# MOM-analog-ins_one-layer_v08.net
KiCad netlist of a schematic drawn in EAGLE
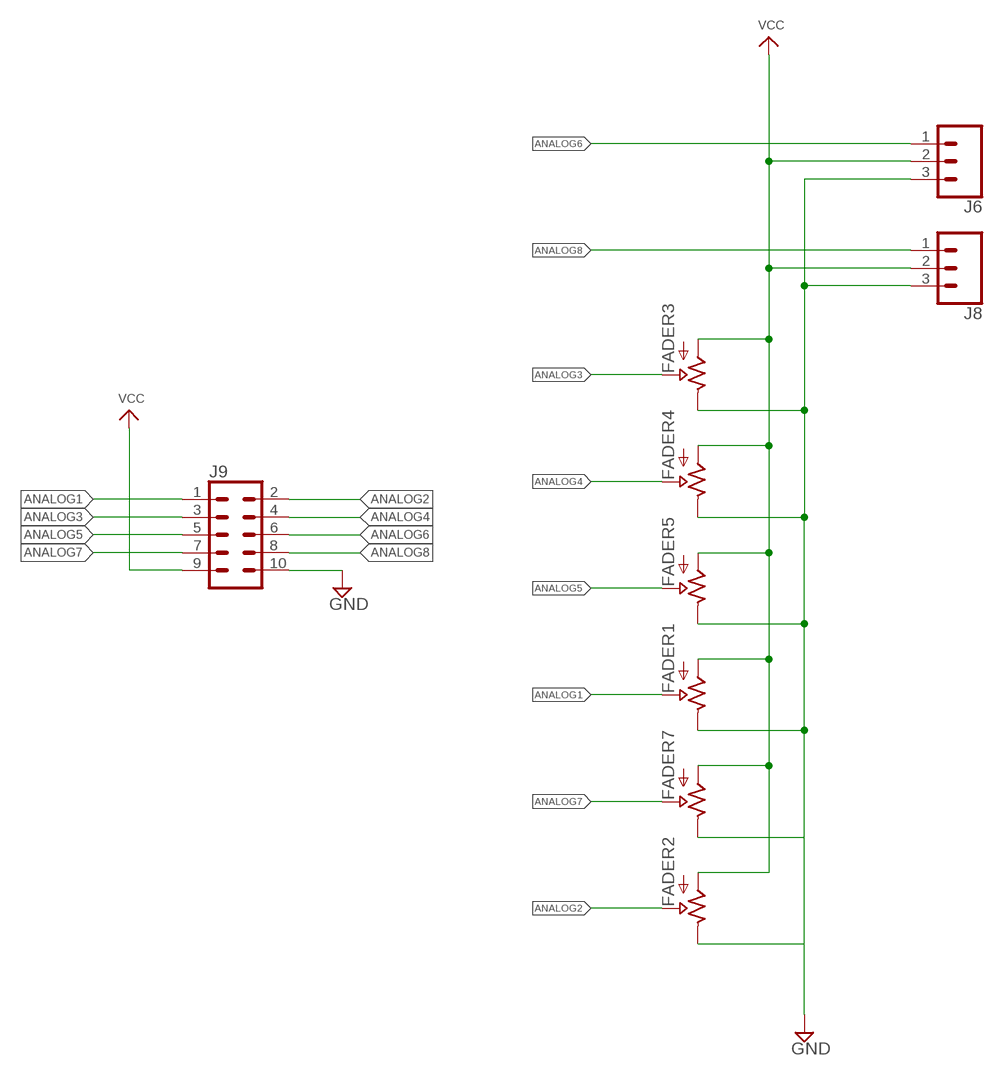
[diagram p0: schematic, sheet 1]

(export (version "E")
  (design (tool "Eeschema 10.0.6"))
  (components
    (comp (ref "FADER1")
      (value "POTTRIMPOT-DIGIKEY")
      (footprint "eagle-import:TRIMPOT-DIGIKEY")
      (libsource (lib "eagle-import") (part "POTTRIMPOT-DIGIKEY"))
    )
    (comp (ref "FADER2")
      (value "POTTRIMPOT-DIGIKEY")
      (footprint "eagle-import:TRIMPOT-DIGIKEY")
      (libsource (lib "eagle-import") (part "POTTRIMPOT-DIGIKEY"))
    )
    (comp (ref "FADER3")
      (value "POTTRIMPOT-DIGIKEY")
      (footprint "eagle-import:TRIMPOT-DIGIKEY")
      (libsource (lib "eagle-import") (part "POTTRIMPOT-DIGIKEY"))
    )
    (comp (ref "FADER4")
      (value "POTTRIMPOT-DIGIKEY")
      (footprint "eagle-import:TRIMPOT-DIGIKEY")
      (libsource (lib "eagle-import") (part "POTTRIMPOT-DIGIKEY"))
    )
    (comp (ref "FADER5")
      (value "POTTRIMPOT-DIGIKEY")
      (footprint "eagle-import:TRIMPOT-DIGIKEY")
      (libsource (lib "eagle-import") (part "POTTRIMPOT-DIGIKEY"))
    )
    (comp (ref "FADER7")
      (value "POTTRIMPOT-DIGIKEY")
      (footprint "eagle-import:TRIMPOT-DIGIKEY")
      (libsource (lib "eagle-import") (part "POTTRIMPOT-DIGIKEY"))
    )
    (comp (ref "J6")
      (value "CONN_03LOCK")
      (footprint "eagle-import:1X03_LOCK")
      (libsource (lib "eagle-import") (part "CONN_03LOCK"))
    )
    (comp (ref "J8")
      (value "CONN_03LOCK")
      (footprint "eagle-import:1X03_LOCK")
      (libsource (lib "eagle-import") (part "CONN_03LOCK"))
    )
    (comp (ref "J9")
      (value "CONN_05X2SHD_LOCK")
      (footprint "eagle-import:2X5-SHROUDED_LOCK")
      (libsource (lib "eagle-import") (part "CONN_05X2SHD_LOCK"))
    )
  )
  (nets
    (net (code "1") (name "ANALOG1") (class "Default")
      (node (ref "FADER1") (pin "2") (pinfunction "WIPER_2") (pintype "passive"))
      (node (ref "J9") (pin "1") (pinfunction "1_1") (pintype "passive"))
    )
    (net (code "2") (name "ANALOG2") (class "Default")
      (node (ref "FADER2") (pin "2") (pinfunction "WIPER_2") (pintype "passive"))
      (node (ref "J9") (pin "2") (pinfunction "2_2") (pintype "passive"))
    )
    (net (code "3") (name "ANALOG3") (class "Default")
      (node (ref "FADER3") (pin "2") (pinfunction "WIPER_2") (pintype "passive"))
      (node (ref "J9") (pin "3") (pinfunction "3_3") (pintype "passive"))
    )
    (net (code "4") (name "ANALOG4") (class "Default")
      (node (ref "FADER4") (pin "2") (pinfunction "WIPER_2") (pintype "passive"))
      (node (ref "J9") (pin "4") (pinfunction "4_4") (pintype "passive"))
    )
    (net (code "5") (name "ANALOG5") (class "Default")
      (node (ref "FADER5") (pin "2") (pinfunction "WIPER_2") (pintype "passive"))
      (node (ref "J9") (pin "5") (pinfunction "5_5") (pintype "passive"))
    )
    (net (code "6") (name "ANALOG6") (class "Default")
      (node (ref "J6") (pin "1") (pinfunction "1_1") (pintype "passive"))
      (node (ref "J9") (pin "6") (pinfunction "6_6") (pintype "passive"))
    )
    (net (code "7") (name "ANALOG7") (class "Default")
      (node (ref "FADER7") (pin "2") (pinfunction "WIPER_2") (pintype "passive"))
      (node (ref "J9") (pin "7") (pinfunction "7_7") (pintype "passive"))
    )
    (net (code "8") (name "ANALOG8") (class "Default")
      (node (ref "J8") (pin "1") (pinfunction "1_1") (pintype "passive"))
      (node (ref "J9") (pin "8") (pinfunction "8_8") (pintype "passive"))
    )
    (net (code "9") (name "GND") (class "Default")
      (node (ref "FADER1") (pin "3") (pinfunction "OUT_3") (pintype "passive"))
      (node (ref "FADER2") (pin "3") (pinfunction "OUT_3") (pintype "passive"))
      (node (ref "FADER3") (pin "3") (pinfunction "OUT_3") (pintype "passive"))
      (node (ref "FADER4") (pin "3") (pinfunction "OUT_3") (pintype "passive"))
      (node (ref "FADER5") (pin "3") (pinfunction "OUT_3") (pintype "passive"))
      (node (ref "FADER7") (pin "3") (pinfunction "OUT_3") (pintype "passive"))
      (node (ref "J6") (pin "3") (pinfunction "3_3") (pintype "passive"))
      (node (ref "J8") (pin "3") (pinfunction "3_3") (pintype "passive"))
      (node (ref "J9") (pin "10") (pinfunction "10_10") (pintype "passive"))
    )
    (net (code "10") (name "VCC") (class "Default")
      (node (ref "FADER1") (pin "1") (pinfunction "IN_1") (pintype "passive"))
      (node (ref "FADER2") (pin "1") (pinfunction "IN_1") (pintype "passive"))
      (node (ref "FADER3") (pin "1") (pinfunction "IN_1") (pintype "passive"))
      (node (ref "FADER4") (pin "1") (pinfunction "IN_1") (pintype "passive"))
      (node (ref "FADER5") (pin "1") (pinfunction "IN_1") (pintype "passive"))
      (node (ref "FADER7") (pin "1") (pinfunction "IN_1") (pintype "passive"))
      (node (ref "J6") (pin "2") (pinfunction "2_2") (pintype "passive"))
      (node (ref "J8") (pin "2") (pinfunction "2_2") (pintype "passive"))
      (node (ref "J9") (pin "9") (pinfunction "9_9") (pintype "passive"))
    )
  )
)
